# ESP12_Dev.net
KiCad netlist of a schematic drawn in EAGLE
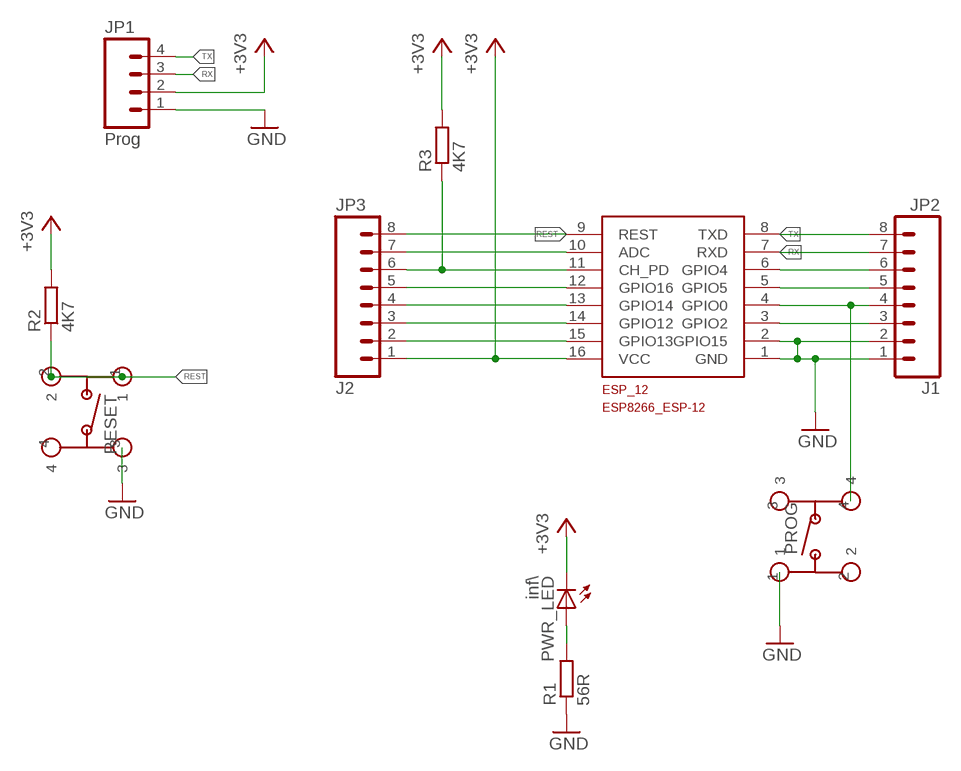
[diagram p0: schematic, sheet 1]

(export (version "E")
  (design (tool "Eeschema 10.0.6"))
  (components
    (comp (ref "ESP_12")
      (value "ESP8266_ESP-12")
      (footprint "eagle-import:ESP8266-ESP12")
      (libsource (lib "eagle-import") (part "ESP8266_ESP-12"))
    )
    (comp (ref "JP1")
      (value "Prog")
      (footprint "eagle-import:1X04_LOCK")
      (libsource (lib "eagle-import") (part "M04LOCK"))
    )
    (comp (ref "JP2")
      (value "J1")
      (footprint "eagle-import:1X08_LOCK")
      (libsource (lib "eagle-import") (part "M08LOCK"))
    )
    (comp (ref "JP3")
      (value "J2")
      (footprint "eagle-import:1X08_LOCK")
      (libsource (lib "eagle-import") (part "M08LOCK"))
    )
    (comp (ref "PROG")
      (value "TACTILE-SWITCH-SMD")
      (footprint "eagle-import:TACTILE-SWITCH-SMD")
      (libsource (lib "eagle-import") (part "TACTILE-SWITCH-SMD"))
    )
    (comp (ref "PWR_LED")
      (value "inf\\")
      (footprint "eagle-import:CHIPLED_0805")
      (libsource (lib "eagle-import") (part "LEDCHIPLED_0805"))
    )
    (comp (ref "R1")
      (value "56R")
      (footprint "eagle-import:R0805")
      (libsource (lib "eagle-import") (part "R-EU_R0805"))
    )
    (comp (ref "R2")
      (value "4K7")
      (footprint "eagle-import:R0805")
      (libsource (lib "eagle-import") (part "R-EU_R0805"))
    )
    (comp (ref "R3")
      (value "4K7")
      (footprint "eagle-import:R0805")
      (libsource (lib "eagle-import") (part "R-EU_R0805"))
    )
    (comp (ref "RESET")
      (value "TACTILE-SWITCH-SMD")
      (footprint "eagle-import:TACTILE-SWITCH-SMD")
      (libsource (lib "eagle-import") (part "TACTILE-SWITCH-SMD"))
    )
  )
  (nets
    (net (code "1") (name "+3V3") (class "Default")
      (node (ref "ESP_12") (pin "16") (pinfunction "VCC_16") (pintype "bidirectional"))
      (node (ref "JP1") (pin "2") (pinfunction "2_2") (pintype "passive"))
      (node (ref "JP3") (pin "1") (pinfunction "1_1") (pintype "passive"))
      (node (ref "PWR_LED") (pin "C") (pinfunction "C_C") (pintype "passive"))
      (node (ref "R2") (pin "2") (pinfunction "2_2") (pintype "passive"))
      (node (ref "R3") (pin "2") (pinfunction "2_2") (pintype "passive"))
    )
    (net (code "2") (name "GND") (class "Default")
      (node (ref "ESP_12") (pin "1") (pinfunction "GND_1") (pintype "bidirectional"))
      (node (ref "ESP_12") (pin "2") (pinfunction "GPIO15_2") (pintype "bidirectional"))
      (node (ref "JP1") (pin "1") (pinfunction "1_1") (pintype "passive"))
      (node (ref "JP2") (pin "1") (pinfunction "1_1") (pintype "passive"))
      (node (ref "JP2") (pin "2") (pinfunction "2_2") (pintype "passive"))
      (node (ref "PROG") (pin "1") (pinfunction "1_1") (pintype "bidirectional"))
      (node (ref "R1") (pin "1") (pinfunction "1_1") (pintype "passive"))
      (node (ref "RESET") (pin "3") (pinfunction "3_3") (pintype "bidirectional"))
    )
    (net (code "3") (name "Net-(ESP_12-ADC)") (class "Default")
      (node (ref "ESP_12") (pin "10") (pinfunction "ADC_10") (pintype "bidirectional"))
      (node (ref "JP3") (pin "7") (pinfunction "7_7") (pintype "passive"))
    )
    (net (code "4") (name "Net-(ESP_12-CH_PD)") (class "Default")
      (node (ref "ESP_12") (pin "11") (pinfunction "CH_PD_11") (pintype "bidirectional"))
      (node (ref "JP3") (pin "6") (pinfunction "6_6") (pintype "passive"))
      (node (ref "R3") (pin "1") (pinfunction "1_1") (pintype "passive"))
    )
    (net (code "5") (name "Net-(ESP_12-GPIO0)") (class "Default")
      (node (ref "ESP_12") (pin "4") (pinfunction "GPIO0_4") (pintype "bidirectional"))
      (node (ref "JP2") (pin "4") (pinfunction "4_4") (pintype "passive"))
      (node (ref "PROG") (pin "4") (pinfunction "4_4") (pintype "bidirectional"))
    )
    (net (code "6") (name "Net-(ESP_12-GPIO2)") (class "Default")
      (node (ref "ESP_12") (pin "3") (pinfunction "GPIO2_3") (pintype "bidirectional"))
      (node (ref "JP2") (pin "3") (pinfunction "3_3") (pintype "passive"))
    )
    (net (code "7") (name "Net-(ESP_12-GPIO4)") (class "Default")
      (node (ref "ESP_12") (pin "6") (pinfunction "GPIO4_6") (pintype "bidirectional"))
      (node (ref "JP2") (pin "6") (pinfunction "6_6") (pintype "passive"))
    )
    (net (code "8") (name "Net-(ESP_12-GPIO5)") (class "Default")
      (node (ref "ESP_12") (pin "5") (pinfunction "GPIO5_5") (pintype "bidirectional"))
      (node (ref "JP2") (pin "5") (pinfunction "5_5") (pintype "passive"))
    )
    (net (code "9") (name "Net-(ESP_12-GPIO12)") (class "Default")
      (node (ref "ESP_12") (pin "14") (pinfunction "GPIO12_14") (pintype "bidirectional"))
      (node (ref "JP3") (pin "3") (pinfunction "3_3") (pintype "passive"))
    )
    (net (code "10") (name "Net-(ESP_12-GPIO13)") (class "Default")
      (node (ref "ESP_12") (pin "15") (pinfunction "GPIO13_15") (pintype "bidirectional"))
      (node (ref "JP3") (pin "2") (pinfunction "2_2") (pintype "passive"))
    )
    (net (code "11") (name "Net-(ESP_12-GPIO14)") (class "Default")
      (node (ref "ESP_12") (pin "13") (pinfunction "GPIO14_13") (pintype "bidirectional"))
      (node (ref "JP3") (pin "4") (pinfunction "4_4") (pintype "passive"))
    )
    (net (code "12") (name "Net-(ESP_12-GPIO16)") (class "Default")
      (node (ref "ESP_12") (pin "12") (pinfunction "GPIO16_12") (pintype "bidirectional"))
      (node (ref "JP3") (pin "5") (pinfunction "5_5") (pintype "passive"))
    )
    (net (code "13") (name "Net-(PWR_LED-PadA)") (class "Default")
      (node (ref "PWR_LED") (pin "A") (pinfunction "A_A") (pintype "passive"))
      (node (ref "R1") (pin "2") (pinfunction "2_2") (pintype "passive"))
    )
    (net (code "14") (name "REST") (class "Default")
      (node (ref "ESP_12") (pin "9") (pinfunction "REST_9") (pintype "bidirectional"))
      (node (ref "JP3") (pin "8") (pinfunction "8_8") (pintype "passive"))
      (node (ref "R2") (pin "1") (pinfunction "1_1") (pintype "passive"))
      (node (ref "RESET") (pin "1") (pinfunction "1_1") (pintype "bidirectional"))
      (node (ref "RESET") (pin "2") (pinfunction "2_2") (pintype "bidirectional"))
    )
    (net (code "15") (name "RX") (class "Default")
      (node (ref "ESP_12") (pin "7") (pinfunction "RXD_7") (pintype "bidirectional"))
      (node (ref "JP1") (pin "3") (pinfunction "3_3") (pintype "passive"))
      (node (ref "JP2") (pin "7") (pinfunction "7_7") (pintype "passive"))
    )
    (net (code "16") (name "TX") (class "Default")
      (node (ref "ESP_12") (pin "8") (pinfunction "TXD_8") (pintype "bidirectional"))
      (node (ref "JP1") (pin "4") (pinfunction "4_4") (pintype "passive"))
      (node (ref "JP2") (pin "8") (pinfunction "8_8") (pintype "passive"))
    )
    (net (code "17") (name "unconnected-(PROG-Pad2)") (class "Default")
      (node (ref "PROG") (pin "2") (pinfunction "2_2") (pintype "bidirectional"))
    )
    (net (code "18") (name "unconnected-(PROG-Pad3)") (class "Default")
      (node (ref "PROG") (pin "3") (pinfunction "3_3") (pintype "bidirectional"))
    )
    (net (code "19") (name "unconnected-(RESET-Pad4)") (class "Default")
      (node (ref "RESET") (pin "4") (pinfunction "4_4") (pintype "bidirectional"))
    )
  )
)
